# motors.net
KiCad netlist of a schematic drawn in Altium Designer
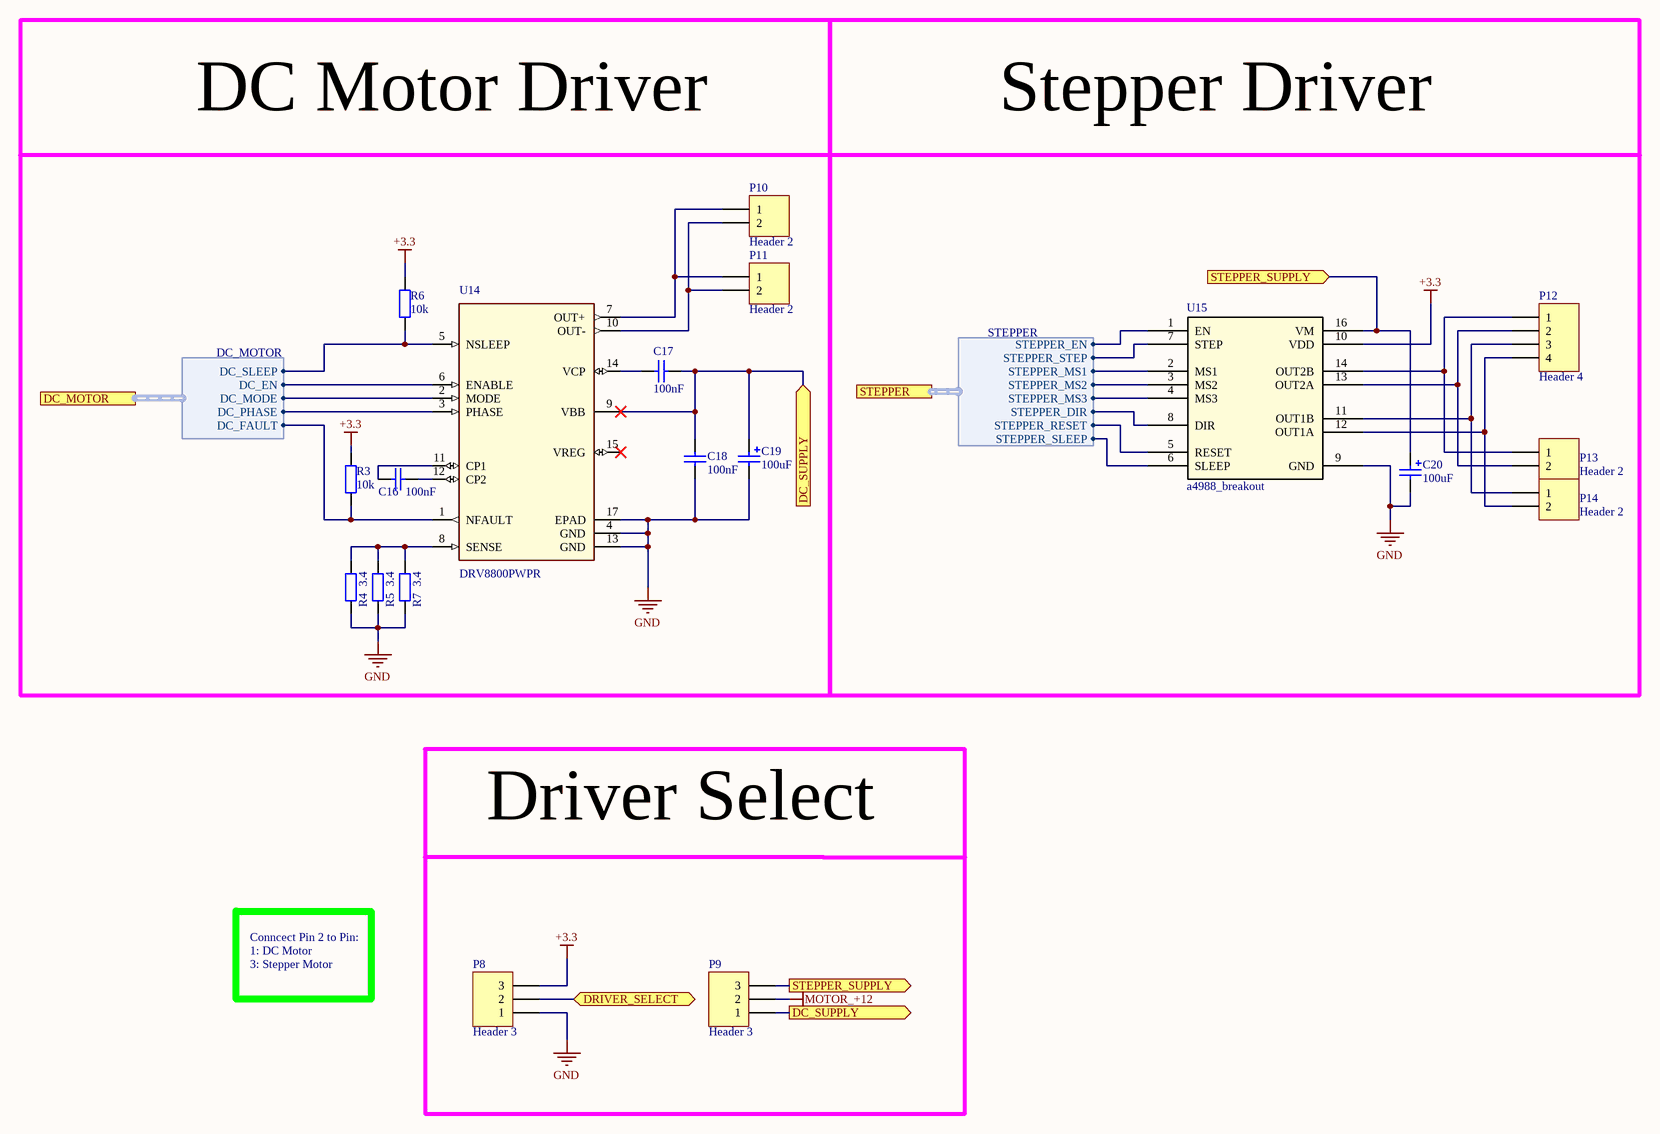
[diagram p0: motors.SchDoc]

(export (version "E")
  (design (tool "Eeschema 10.0.6"))
  (components
    (comp (ref "C16")
      (value "100nF")
      (footprint "CAP_0603i_1608m -N")
      (description "capacitor")
      (libsource (lib "IDSC std generic parts") (part "Cap"))
    )
    (comp (ref "C17")
      (value "100nF")
      (footprint "CAP_0603i_1608m -N")
      (description "capacitor")
      (libsource (lib "IDSC std generic parts") (part "Cap"))
    )
    (comp (ref "C18")
      (value "100nF")
      (footprint "CAP_0603i_1608m -N")
      (description "capacitor")
      (libsource (lib "IDSC std generic parts") (part "Cap"))
    )
    (comp (ref "C19")
      (value "100uF")
      (footprint "Cap_F-Type-Package")
      (description "Polarised capacitor (e.g. Electrolytic )")
      (libsource (lib "IDSC std generic parts") (part "Cap pol"))
    )
    (comp (ref "C20")
      (value "100uF")
      (footprint "Cap_F-Type-Package")
      (description "Polarised capacitor (e.g. Electrolytic )")
      (libsource (lib "IDSC std generic parts") (part "Cap pol"))
    )
    (comp (ref "P8")
      (value "Header 3")
      (footprint "HDR1X3")
      (description "Header, 3-Pin")
      (libsource (lib "IDSC std connectors") (part "Header 3"))
    )
    (comp (ref "P9")
      (value "Header 3")
      (footprint "HDR1X3")
      (description "Header, 3-Pin")
      (libsource (lib "IDSC std connectors") (part "Header 3"))
    )
    (comp (ref "P10")
      (value "Header 2")
      (footprint "HDR1X2")
      (description "Header, 2-Pin")
      (libsource (lib "IDSC std connectors") (part "Header 2"))
    )
    (comp (ref "P11")
      (value "Header 2")
      (footprint "3.5MM Phoenix Contact 1984617")
      (description "Header, 2-Pin")
      (libsource (lib "IDSC std connectors") (part "Header 2"))
    )
    (comp (ref "P12")
      (value "Header 4")
      (footprint "HDR1X4")
      (description "Header, 4-Pin")
      (libsource (lib "IDSC std connectors") (part "Header 4"))
    )
    (comp (ref "P13")
      (value "Header 2")
      (footprint "3.5MM Phoenix Contact 1984617")
      (description "Header, 2-Pin")
      (libsource (lib "IDSC std connectors") (part "Header 2"))
    )
    (comp (ref "P14")
      (value "Header 2")
      (footprint "3.5MM Phoenix Contact 1984617")
      (description "Header, 2-Pin")
      (libsource (lib "IDSC std connectors") (part "Header 2"))
    )
    (comp (ref "R3")
      (value "10k")
      (footprint "RES_0603i_1608m -N")
      (description "Resistor")
      (libsource (lib "IDSC std generic parts") (part "Res"))
    )
    (comp (ref "R4")
      (value "3.4")
      (footprint "RES_1206i_C3216m -N")
      (description "Resistor")
      (libsource (lib "IDSC std generic parts") (part "Res"))
    )
    (comp (ref "R5")
      (value "3.4")
      (footprint "RES_1206i_C3216m -N")
      (description "Resistor")
      (libsource (lib "IDSC std generic parts") (part "Res"))
    )
    (comp (ref "R6")
      (value "10k")
      (footprint "RES_0603i_1608m -N")
      (description "Resistor")
      (libsource (lib "IDSC std generic parts") (part "Res"))
    )
    (comp (ref "R7")
      (value "3.4")
      (footprint "RES_1206i_C3216m -N")
      (description "Resistor")
      (libsource (lib "IDSC std generic parts") (part "Res"))
    )
    (comp (ref "U14")
      (value "DRV8800PWPR")
      (footprint "*SOP65P640X120-17N")
      (libsource (lib "BMA_lib") (part "DRV8800PWPR"))
    )
    (comp (ref "U15")
      (value "a4988_breakout")
      (footprint "a4988_breakout")
      (libsource (lib "BMA_lib") (part "a4988_breakout"))
    )
  )
  (nets
    (net (code "3") (name "+3.3") (class "Default")
      (node (ref "P8") (pin "3") (pinfunction "3_3") (pintype "passive"))
      (node (ref "R3") (pin "2") (pinfunction "2_2") (pintype "passive"))
      (node (ref "R6") (pin "2") (pinfunction "2_2") (pintype "passive"))
      (node (ref "U15") (pin "10") (pinfunction "VDD_10") (pintype "passive"))
    )
    (net (code "4") (name "/DC_EN") (class "Default")
      (node (ref "U14") (pin "6") (pinfunction "ENABLE_6") (pintype "input"))
    )
    (net (code "5") (name "/DC_FAULT") (class "Default")
      (node (ref "R3") (pin "1") (pinfunction "1_1") (pintype "passive"))
      (node (ref "U14") (pin "1") (pinfunction "NFAULT_1") (pintype "output"))
    )
    (net (code "6") (name "/DC_MODE") (class "Default")
      (node (ref "U14") (pin "2") (pinfunction "MODE_2") (pintype "input"))
    )
    (net (code "7") (name "/DC_PHASE") (class "Default")
      (node (ref "U14") (pin "3") (pinfunction "PHASE_3") (pintype "input"))
    )
    (net (code "8") (name "/DC_SLEEP") (class "Default")
      (node (ref "R6") (pin "1") (pinfunction "1_1") (pintype "passive"))
      (node (ref "U14") (pin "5") (pinfunction "NSLEEP_5") (pintype "input"))
    )
    (net (code "9") (name "/DC_SUPPLY") (class "Default")
      (node (ref "C17") (pin "1") (pinfunction "1_1") (pintype "passive"))
      (node (ref "C18") (pin "2") (pinfunction "2_2") (pintype "passive"))
      (node (ref "C19") (pin "1") (pinfunction "1_1") (pintype "passive"))
      (node (ref "P9") (pin "1") (pinfunction "1_1") (pintype "passive"))
      (node (ref "U14") (pin "9") (pinfunction "VBB_9") (pintype "power_in"))
    )
    (net (code "10") (name "/DRIVER_SELECT") (class "Default")
      (node (ref "P8") (pin "2") (pinfunction "2_2") (pintype "passive"))
    )
    (net (code "11") (name "/STEPPER_DIR") (class "Default")
      (node (ref "U15") (pin "8") (pinfunction "DIR_8") (pintype "passive"))
    )
    (net (code "12") (name "/STEPPER_EN") (class "Default")
      (node (ref "U15") (pin "1") (pinfunction "EN_1") (pintype "passive"))
    )
    (net (code "13") (name "/STEPPER_MS1") (class "Default")
      (node (ref "U15") (pin "2") (pinfunction "MS1_2") (pintype "passive"))
    )
    (net (code "14") (name "/STEPPER_MS2") (class "Default")
      (node (ref "U15") (pin "3") (pinfunction "MS2_3") (pintype "passive"))
    )
    (net (code "15") (name "/STEPPER_MS3") (class "Default")
      (node (ref "U15") (pin "4") (pinfunction "MS3_4") (pintype "passive"))
    )
    (net (code "16") (name "/STEPPER_RESET") (class "Default")
      (node (ref "U15") (pin "5") (pinfunction "RESET_5") (pintype "passive"))
    )
    (net (code "17") (name "/STEPPER_SLEEP") (class "Default")
      (node (ref "U15") (pin "6") (pinfunction "SLEEP_6") (pintype "passive"))
    )
    (net (code "18") (name "/STEPPER_STEP") (class "Default")
      (node (ref "U15") (pin "7") (pinfunction "STEP_7") (pintype "passive"))
    )
    (net (code "19") (name "/STEPPER_SUPPLY") (class "Default")
      (node (ref "C20") (pin "1") (pinfunction "1_1") (pintype "passive"))
      (node (ref "P9") (pin "3") (pinfunction "3_3") (pintype "passive"))
      (node (ref "U15") (pin "16") (pinfunction "VM_16") (pintype "passive"))
    )
    (net (code "22") (name "GND") (class "Default")
      (node (ref "C18") (pin "1") (pinfunction "1_1") (pintype "passive"))
      (node (ref "C19") (pin "2") (pinfunction "2_2") (pintype "passive"))
      (node (ref "C20") (pin "2") (pinfunction "2_2") (pintype "passive"))
      (node (ref "P8") (pin "1") (pinfunction "1_1") (pintype "passive"))
      (node (ref "R4") (pin "1") (pinfunction "1_1") (pintype "passive"))
      (node (ref "R5") (pin "1") (pinfunction "1_1") (pintype "passive"))
      (node (ref "R7") (pin "1") (pinfunction "1_1") (pintype "passive"))
      (node (ref "U14") (pin "13") (pinfunction "GND_13") (pintype "power_in"))
      (node (ref "U14") (pin "17") (pinfunction "EPAD_17") (pintype "power_in"))
      (node (ref "U14") (pin "4") (pinfunction "GND_4") (pintype "power_in"))
      (node (ref "U15") (pin "9") (pinfunction "GND_9") (pintype "passive"))
    )
    (net (code "23") (name "MOTOR_+12") (class "Default")
      (node (ref "P9") (pin "2") (pinfunction "2_2") (pintype "passive"))
    )
    (net (code "24") (name "Net-(U14-CP1)") (class "Default")
      (node (ref "C16") (pin "1") (pinfunction "1_1") (pintype "passive"))
      (node (ref "U14") (pin "11") (pinfunction "CP1_11") (pintype "bidirectional"))
    )
    (net (code "25") (name "Net-(U14-CP2)") (class "Default")
      (node (ref "C16") (pin "2") (pinfunction "2_2") (pintype "passive"))
      (node (ref "U14") (pin "12") (pinfunction "CP2_12") (pintype "bidirectional"))
    )
    (net (code "26") (name "Net-(U14-OUT+)") (class "Default")
      (node (ref "P10") (pin "1") (pinfunction "1_1") (pintype "passive"))
      (node (ref "P11") (pin "1") (pinfunction "1_1") (pintype "passive"))
      (node (ref "U14") (pin "7") (pinfunction "OUT+_7") (pintype "output"))
    )
    (net (code "27") (name "Net-(U14-OUT-)") (class "Default")
      (node (ref "P10") (pin "2") (pinfunction "2_2") (pintype "passive"))
      (node (ref "P11") (pin "2") (pinfunction "2_2") (pintype "passive"))
      (node (ref "U14") (pin "10") (pinfunction "OUT-_10") (pintype "output"))
    )
    (net (code "28") (name "Net-(U14-SENSE)") (class "Default")
      (node (ref "R4") (pin "2") (pinfunction "2_2") (pintype "passive"))
      (node (ref "R5") (pin "2") (pinfunction "2_2") (pintype "passive"))
      (node (ref "R7") (pin "2") (pinfunction "2_2") (pintype "passive"))
      (node (ref "U14") (pin "8") (pinfunction "SENSE_8") (pintype "input"))
    )
    (net (code "29") (name "Net-(U14-VCP)") (class "Default")
      (node (ref "C17") (pin "2") (pinfunction "2_2") (pintype "passive"))
      (node (ref "U14") (pin "14") (pinfunction "VCP_14") (pintype "bidirectional"))
    )
    (net (code "30") (name "Net-(U15-OUT1A)") (class "Default")
      (node (ref "P12") (pin "4") (pinfunction "4_4") (pintype "passive"))
      (node (ref "P14") (pin "2") (pinfunction "2_2") (pintype "passive"))
      (node (ref "U15") (pin "12") (pinfunction "OUT1A_12") (pintype "passive"))
    )
    (net (code "31") (name "Net-(U15-OUT1B)") (class "Default")
      (node (ref "P12") (pin "3") (pinfunction "3_3") (pintype "passive"))
      (node (ref "P14") (pin "1") (pinfunction "1_1") (pintype "passive"))
      (node (ref "U15") (pin "11") (pinfunction "OUT1B_11") (pintype "passive"))
    )
    (net (code "32") (name "Net-(U15-OUT2A)") (class "Default")
      (node (ref "P12") (pin "2") (pinfunction "2_2") (pintype "passive"))
      (node (ref "P13") (pin "2") (pinfunction "2_2") (pintype "passive"))
      (node (ref "U15") (pin "13") (pinfunction "OUT2A_13") (pintype "passive"))
    )
    (net (code "33") (name "Net-(U15-OUT2B)") (class "Default")
      (node (ref "P12") (pin "1") (pinfunction "1_1") (pintype "passive"))
      (node (ref "P13") (pin "1") (pinfunction "1_1") (pintype "passive"))
      (node (ref "U15") (pin "14") (pinfunction "OUT2B_14") (pintype "passive"))
    )
    (net (code "34") (name "unconnected-(U14-VREG-Pad15)") (class "Default")
      (node (ref "U14") (pin "15") (pinfunction "VREG_15") (pintype "bidirectional+no_connect"))
    )
  )
)
